# ESP32.net
KiCad netlist of a schematic drawn in Altium Designer
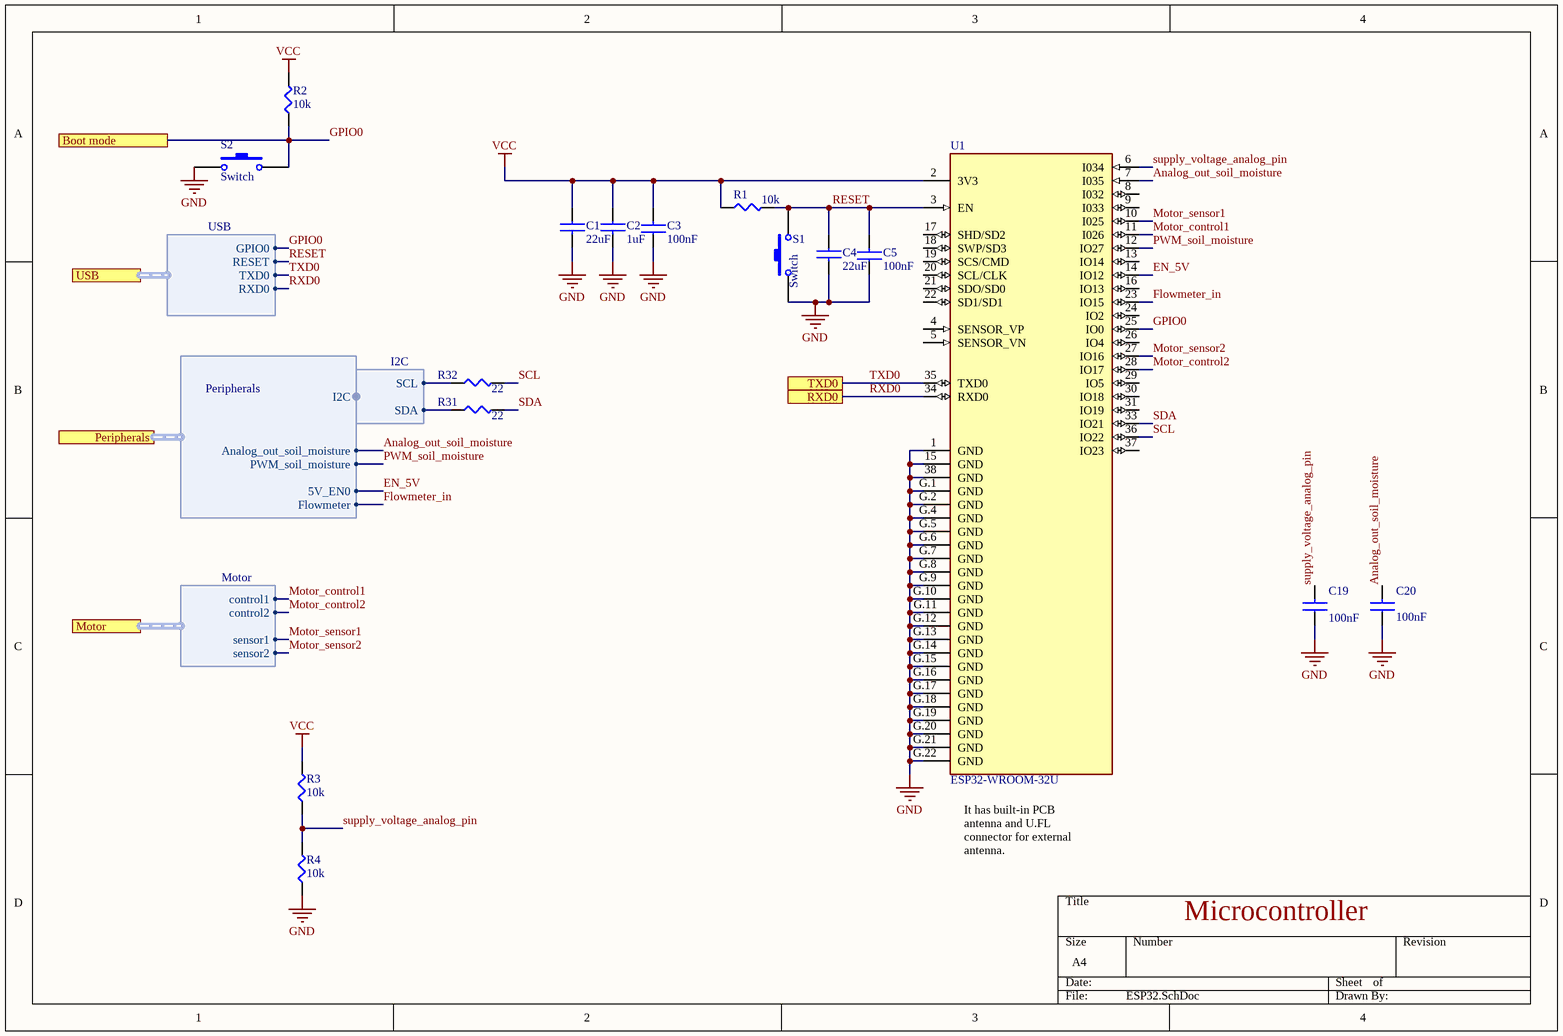
[diagram p0: ESP32.SchDoc]

(export (version "E")
  (design (tool "Eeschema 10.0.6"))
  (components
    (comp (ref "C1")
      (value "22uF")
      (footprint "CAPC200X125X110L50N")
      (fields (field (name "LCSC PART #") "C59461"))
      (libsource (lib "WateringSystem_lib") (part "Capacitor"))
    )
    (comp (ref "C2")
      (value "1uF")
      (footprint "CAPC200X125X110L50N")
      (fields (field (name "LCSC PART #") "C15849"))
      (libsource (lib "WateringSystem_lib") (part "Capacitor"))
    )
    (comp (ref "C3")
      (value "100nF")
      (footprint "CAPC160X80X90L35N")
      (fields (field (name "LCSC PART #") "C14663"))
      (libsource (lib "WateringSystem_lib") (part "Capacitor"))
    )
    (comp (ref "C4")
      (value "22uF")
      (footprint "CAPC200X125X110L50N")
      (fields (field (name "LCSC PART #") "C59461"))
      (libsource (lib "WateringSystem_lib") (part "Capacitor"))
    )
    (comp (ref "C5")
      (value "100nF")
      (footprint "CAPC160X80X90L35N")
      (fields (field (name "LCSC PART #") "C14663"))
      (libsource (lib "WateringSystem_lib") (part "Capacitor"))
    )
    (comp (ref "C19")
      (value "100nF")
      (footprint "CAPC160X80X90L35N")
      (fields (field (name "LCSC PART #") "C14663"))
      (libsource (lib "WateringSystem_lib") (part "Capacitor"))
    )
    (comp (ref "C20")
      (value "100nF")
      (footprint "CAPC160X80X90L35N")
      (fields (field (name "LCSC PART #") "C14663"))
      (libsource (lib "WateringSystem_lib") (part "Capacitor"))
    )
    (comp (ref "R1")
      (value "10k")
      (footprint "RESC200X125X70L40N")
      (fields (field (name "LCSC PART #") "C17414"))
      (libsource (lib "WateringSystem_lib") (part "Resistor"))
    )
    (comp (ref "R2")
      (value "10k")
      (footprint "WateringSystem_lib:RESC200X125X70L40N")
      (fields (field (name "LCSC PART #") "C17414"))
      (libsource (lib "WateringSystem_lib") (part "Resistor"))
    )
    (comp (ref "R3")
      (value "10k")
      (footprint "RESC200X125X70L40N")
      (fields (field (name "LCSC PART #") "C17414"))
      (libsource (lib "WateringSystem_lib") (part "Resistor"))
    )
    (comp (ref "R4")
      (value "10k")
      (footprint "RESC200X125X70L40N")
      (fields (field (name "LCSC PART #") "C17414"))
      (libsource (lib "WateringSystem_lib") (part "Resistor"))
    )
    (comp (ref "R31")
      (value "22")
      (footprint "RESC160X80X90L30N")
      (fields (field (name "LCSC PART #") "C23345"))
      (libsource (lib "WateringSystem_lib") (part "Resistor"))
    )
    (comp (ref "R32")
      (value "22")
      (footprint "RESC160X80X90L30N")
      (fields (field (name "LCSC PART #") "C23345"))
      (libsource (lib "WateringSystem_lib") (part "Resistor"))
    )
    (comp (ref "S1")
      (value "Switch")
      (footprint "SKRKAEE020")
      (fields (field (name "LCSC PART #") "C115357") (field (name "PUBLISHER") "Altium Limited"))
      (libsource (lib "WateringSystem_lib") (part "Switch"))
    )
    (comp (ref "S2")
      (value "Switch")
      (footprint "SKRKAEE020")
      (fields (field (name "LCSC PART #") "C115357") (field (name "PUBLISHER") "Altium Limited"))
      (libsource (lib "WateringSystem_lib") (part "Switch"))
    )
    (comp (ref "U1")
      (value "ESP32-WROOM-32U")
      (footprint "ESP32-WROOM-32U")
      (fields (field (name "MF") "Espressif Systems") (field (name "LCSC PART #") "C277944"))
      (libsource (lib "WateringSystem_lib") (part "ESP32-WROOM-32U"))
    )
  )
  (nets
    (net (code "4") (name "/Analog_out_soil_moisture") (class "Default")
      (node (ref "C20") (pin "2") (pinfunction "2_2") (pintype "passive"))
      (node (ref "U1") (pin "7") (pinfunction "I035_7") (pintype "input"))
    )
    (net (code "5") (name "/EN_5V") (class "Default")
      (node (ref "U1") (pin "14") (pinfunction "IO12_14") (pintype "bidirectional"))
    )
    (net (code "6") (name "/Flowmeter_in") (class "Default")
      (node (ref "U1") (pin "23") (pinfunction "IO15_23") (pintype "bidirectional"))
    )
    (net (code "7") (name "/GPIO0") (class "Default")
      (node (ref "R2") (pin "1") (pinfunction "1_1") (pintype "passive"))
      (node (ref "S2") (pin "1") (pinfunction "1_1") (pintype "passive"))
      (node (ref "U1") (pin "25") (pinfunction "IO0_25") (pintype "bidirectional"))
    )
    (net (code "8") (name "/Motor_control1") (class "Default")
      (node (ref "U1") (pin "11") (pinfunction "I026_11") (pintype "bidirectional"))
    )
    (net (code "9") (name "/Motor_control2") (class "Default")
      (node (ref "U1") (pin "28") (pinfunction "IO17_28") (pintype "bidirectional"))
    )
    (net (code "10") (name "/Motor_sensor1") (class "Default")
      (node (ref "U1") (pin "10") (pinfunction "I025_10") (pintype "bidirectional"))
    )
    (net (code "11") (name "/Motor_sensor2") (class "Default")
      (node (ref "U1") (pin "27") (pinfunction "IO16_27") (pintype "bidirectional"))
    )
    (net (code "12") (name "/PWM_soil_moisture") (class "Default")
      (node (ref "U1") (pin "12") (pinfunction "IO27_12") (pintype "bidirectional"))
    )
    (net (code "13") (name "/RESET") (class "Default")
      (node (ref "C4") (pin "1") (pinfunction "1_1") (pintype "passive"))
      (node (ref "C5") (pin "2") (pinfunction "2_2") (pintype "passive"))
      (node (ref "R1") (pin "2") (pinfunction "2_2") (pintype "passive"))
      (node (ref "S1") (pin "2") (pinfunction "2_2") (pintype "passive"))
      (node (ref "U1") (pin "3") (pinfunction "EN_3") (pintype "input"))
    )
    (net (code "14") (name "/RXD0") (class "Default")
      (node (ref "U1") (pin "34") (pinfunction "RXD0_34") (pintype "bidirectional"))
    )
    (net (code "15") (name "/SCL") (class "Default")
      (node (ref "R32") (pin "2") (pinfunction "2_2") (pintype "passive"))
      (node (ref "U1") (pin "36") (pinfunction "IO22_36") (pintype "bidirectional"))
    )
    (net (code "16") (name "/SDA") (class "Default")
      (node (ref "R31") (pin "2") (pinfunction "2_2") (pintype "passive"))
      (node (ref "U1") (pin "33") (pinfunction "IO21_33") (pintype "bidirectional"))
    )
    (net (code "17") (name "/TXD0") (class "Default")
      (node (ref "U1") (pin "35") (pinfunction "TXD0_35") (pintype "bidirectional"))
    )
    (net (code "18") (name "/supply_voltage_analog_pin") (class "Default")
      (node (ref "C19") (pin "2") (pinfunction "2_2") (pintype "passive"))
      (node (ref "R3") (pin "1") (pinfunction "1_1") (pintype "passive"))
      (node (ref "R4") (pin "2") (pinfunction "2_2") (pintype "passive"))
      (node (ref "U1") (pin "6") (pinfunction "I034_6") (pintype "input"))
    )
    (net (code "22") (name "GND") (class "Default")
      (node (ref "C1") (pin "2") (pinfunction "2_2") (pintype "passive"))
      (node (ref "C19") (pin "1") (pinfunction "1_1") (pintype "passive"))
      (node (ref "C2") (pin "2") (pinfunction "2_2") (pintype "passive"))
      (node (ref "C20") (pin "1") (pinfunction "1_1") (pintype "passive"))
      (node (ref "C3") (pin "1") (pinfunction "1_1") (pintype "passive"))
      (node (ref "C4") (pin "2") (pinfunction "2_2") (pintype "passive"))
      (node (ref "C5") (pin "1") (pinfunction "1_1") (pintype "passive"))
      (node (ref "R4") (pin "1") (pinfunction "1_1") (pintype "passive"))
      (node (ref "S1") (pin "1") (pinfunction "1_1") (pintype "passive"))
      (node (ref "S2") (pin "2") (pinfunction "2_2") (pintype "passive"))
      (node (ref "U1") (pin "1") (pinfunction "GND_1") (pintype "power_in"))
      (node (ref "U1") (pin "15") (pinfunction "GND_15") (pintype "power_in"))
      (node (ref "U1") (pin "38") (pinfunction "GND_38") (pintype "power_in"))
      (node (ref "U1") (pin "G.1") (pinfunction "GND_G.1") (pintype "power_in"))
      (node (ref "U1") (pin "G.10") (pinfunction "GND_G.10") (pintype "power_in"))
      (node (ref "U1") (pin "G.11") (pinfunction "GND_G.11") (pintype "power_in"))
      (node (ref "U1") (pin "G.12") (pinfunction "GND_G.12") (pintype "power_in"))
      (node (ref "U1") (pin "G.13") (pinfunction "GND_G.13") (pintype "power_in"))
      (node (ref "U1") (pin "G.14") (pinfunction "GND_G.14") (pintype "power_in"))
      (node (ref "U1") (pin "G.15") (pinfunction "GND_G.15") (pintype "power_in"))
      (node (ref "U1") (pin "G.16") (pinfunction "GND_G.16") (pintype "power_in"))
      (node (ref "U1") (pin "G.17") (pinfunction "GND_G.17") (pintype "power_in"))
      (node (ref "U1") (pin "G.18") (pinfunction "GND_G.18") (pintype "power_in"))
      (node (ref "U1") (pin "G.19") (pinfunction "GND_G.19") (pintype "power_in"))
      (node (ref "U1") (pin "G.2") (pinfunction "GND_G.2") (pintype "power_in"))
      (node (ref "U1") (pin "G.20") (pinfunction "GND_G.20") (pintype "power_in"))
      (node (ref "U1") (pin "G.21") (pinfunction "GND_G.21") (pintype "power_in"))
      (node (ref "U1") (pin "G.22") (pinfunction "GND_G.22") (pintype "power_in"))
      (node (ref "U1") (pin "G.4") (pinfunction "GND_G.4") (pintype "power_in"))
      (node (ref "U1") (pin "G.5") (pinfunction "GND_G.5") (pintype "power_in"))
      (node (ref "U1") (pin "G.6") (pinfunction "GND_G.6") (pintype "power_in"))
      (node (ref "U1") (pin "G.7") (pinfunction "GND_G.7") (pintype "power_in"))
      (node (ref "U1") (pin "G.8") (pinfunction "GND_G.8") (pintype "power_in"))
      (node (ref "U1") (pin "G.9") (pinfunction "GND_G.9") (pintype "power_in"))
    )
    (net (code "23") (name "VCC") (class "Default")
      (node (ref "C1") (pin "1") (pinfunction "1_1") (pintype "passive"))
      (node (ref "C2") (pin "1") (pinfunction "1_1") (pintype "passive"))
      (node (ref "C3") (pin "2") (pinfunction "2_2") (pintype "passive"))
      (node (ref "R1") (pin "1") (pinfunction "1_1") (pintype "passive"))
      (node (ref "R2") (pin "2") (pinfunction "2_2") (pintype "passive"))
      (node (ref "R3") (pin "2") (pinfunction "2_2") (pintype "passive"))
      (node (ref "U1") (pin "2") (pinfunction "3V3_2") (pintype "power_in"))
    )
    (net (code "24") (name "unconnected-(R31-Pad1)") (class "Default")
      (node (ref "R31") (pin "1") (pinfunction "1_1") (pintype "passive"))
    )
    (net (code "25") (name "unconnected-(R32-Pad1)") (class "Default")
      (node (ref "R32") (pin "1") (pinfunction "1_1") (pintype "passive"))
    )
    (net (code "26") (name "unconnected-(U1-I032-Pad8)") (class "Default")
      (node (ref "U1") (pin "8") (pinfunction "I032_8") (pintype "bidirectional"))
    )
    (net (code "27") (name "unconnected-(U1-I033-Pad9)") (class "Default")
      (node (ref "U1") (pin "9") (pinfunction "I033_9") (pintype "bidirectional"))
    )
    (net (code "28") (name "unconnected-(U1-IO2-Pad24)") (class "Default")
      (node (ref "U1") (pin "24") (pinfunction "IO2_24") (pintype "bidirectional"))
    )
    (net (code "29") (name "unconnected-(U1-IO4-Pad26)") (class "Default")
      (node (ref "U1") (pin "26") (pinfunction "IO4_26") (pintype "bidirectional"))
    )
    (net (code "30") (name "unconnected-(U1-IO5-Pad29)") (class "Default")
      (node (ref "U1") (pin "29") (pinfunction "IO5_29") (pintype "bidirectional"))
    )
    (net (code "31") (name "unconnected-(U1-IO13-Pad16)") (class "Default")
      (node (ref "U1") (pin "16") (pinfunction "IO13_16") (pintype "bidirectional"))
    )
    (net (code "32") (name "unconnected-(U1-IO14-Pad13)") (class "Default")
      (node (ref "U1") (pin "13") (pinfunction "IO14_13") (pintype "bidirectional"))
    )
    (net (code "33") (name "unconnected-(U1-IO18-Pad30)") (class "Default")
      (node (ref "U1") (pin "30") (pinfunction "IO18_30") (pintype "bidirectional"))
    )
    (net (code "34") (name "unconnected-(U1-IO19-Pad31)") (class "Default")
      (node (ref "U1") (pin "31") (pinfunction "IO19_31") (pintype "bidirectional"))
    )
    (net (code "35") (name "unconnected-(U1-IO23-Pad37)") (class "Default")
      (node (ref "U1") (pin "37") (pinfunction "IO23_37") (pintype "bidirectional"))
    )
    (net (code "36") (name "unconnected-(U1-SCL{slash}CLK-Pad20)") (class "Default")
      (node (ref "U1") (pin "20") (pinfunction "SCL/CLK_20") (pintype "bidirectional"))
    )
    (net (code "37") (name "unconnected-(U1-SCS{slash}CMD-Pad19)") (class "Default")
      (node (ref "U1") (pin "19") (pinfunction "SCS/CMD_19") (pintype "bidirectional"))
    )
    (net (code "38") (name "unconnected-(U1-SD1{slash}SD1-Pad22)") (class "Default")
      (node (ref "U1") (pin "22") (pinfunction "SD1/SD1_22") (pintype "bidirectional"))
    )
    (net (code "39") (name "unconnected-(U1-SDO{slash}SD0-Pad21)") (class "Default")
      (node (ref "U1") (pin "21") (pinfunction "SDO/SD0_21") (pintype "bidirectional"))
    )
    (net (code "40") (name "unconnected-(U1-SENSOR_VN-Pad5)") (class "Default")
      (node (ref "U1") (pin "5") (pinfunction "SENSOR_VN_5") (pintype "input"))
    )
    (net (code "41") (name "unconnected-(U1-SENSOR_VP-Pad4)") (class "Default")
      (node (ref "U1") (pin "4") (pinfunction "SENSOR_VP_4") (pintype "input"))
    )
    (net (code "42") (name "unconnected-(U1-SHD{slash}SD2-Pad17)") (class "Default")
      (node (ref "U1") (pin "17") (pinfunction "SHD/SD2_17") (pintype "bidirectional"))
    )
    (net (code "43") (name "unconnected-(U1-SWP{slash}SD3-Pad18)") (class "Default")
      (node (ref "U1") (pin "18") (pinfunction "SWP/SD3_18") (pintype "bidirectional"))
    )
  )
)
